# 0021.net
KiCad netlist of a schematic drawn in Altium Designer
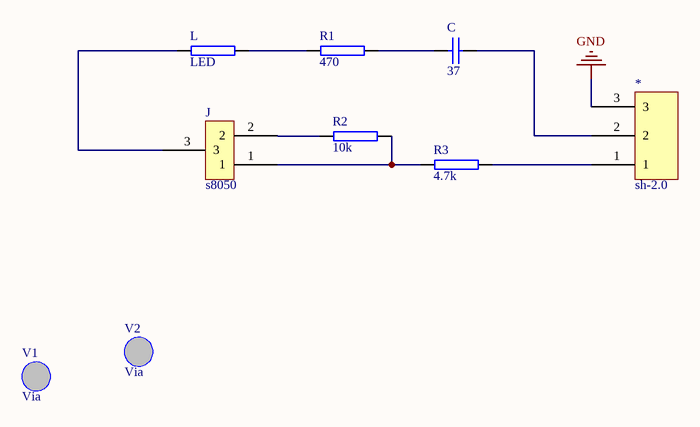
[diagram p0: 0021.SchDoc]

(export (version "E")
  (design (tool "Eeschema 10.0.6"))
  (components
    (comp (ref "*") (value "sh-2.0") (footprint "sh-2.0") (libsource (lib "zhangchong") (part "sh-2.0")))
    (comp (ref "C") (value "37") (footprint "0402") (libsource (lib "gupeng_sch") (part "CAP0402")))
    (comp (ref "J") (value "s8050") (footprint "SOT-23") (libsource (lib "zhangchong") (part "s8050")))
    (comp (ref "L") (value "LED") (footprint "1206") (libsource (lib "PEI_SCH") (part "RES1206")))
    (comp (ref "R1") (value "470") (footprint "0402") (libsource (lib "gupeng_sch") (part "RES0402")))
    (comp (ref "R2") (value "10k") (footprint "0402") (libsource (lib "gupeng_sch") (part "RES0402")))
    (comp (ref "R3") (value "4.7k") (footprint "0402") (libsource (lib "gupeng_sch") (part "RES0402")))
    (comp (ref "V1") (value "Via") (footprint "zhaoyujiu:Via") (libsource (lib "zhaoyujiu") (part "Via")))
    (comp (ref "V2") (value "Via") (footprint "zhaoyujiu:Via") (libsource (lib "zhaoyujiu") (part "Via")))
  )
  (nets
    (net (code "1") (name "GND") (class "Default")
      (node (ref "*") (pin "3") (pinfunction "3_3") (pintype "passive"))
    )
    (net (code "2") (name "Net-(*-Pad1)") (class "Default")
      (node (ref "*") (pin "1") (pinfunction "1_1") (pintype "passive"))
      (node (ref "R3") (pin "2") (pinfunction "2_2") (pintype "passive"))
    )
    (net (code "3") (name "Net-(*-Pad2)") (class "Default")
      (node (ref "*") (pin "2") (pinfunction "2_2") (pintype "passive"))
      (node (ref "C") (pin "2") (pinfunction "2_2") (pintype "passive"))
    )
    (net (code "4") (name "Net-(C-Pad1)") (class "Default")
      (node (ref "C") (pin "1") (pinfunction "1_1") (pintype "passive"))
      (node (ref "R1") (pin "2") (pinfunction "2_2") (pintype "passive"))
    )
    (net (code "5") (name "Net-(J-Pad1)") (class "Default")
      (node (ref "J") (pin "1") (pinfunction "1_1") (pintype "passive"))
      (node (ref "R2") (pin "1") (pinfunction "1_1") (pintype "passive"))
      (node (ref "R3") (pin "1") (pinfunction "1_1") (pintype "passive"))
    )
    (net (code "6") (name "Net-(J-Pad2)") (class "Default")
      (node (ref "J") (pin "2") (pinfunction "2_2") (pintype "passive"))
      (node (ref "R2") (pin "2") (pinfunction "2_2") (pintype "passive"))
    )
    (net (code "7") (name "Net-(J-Pad3)") (class "Default")
      (node (ref "J") (pin "3") (pinfunction "3_3") (pintype "passive"))
      (node (ref "L") (pin "1") (pinfunction "1_1") (pintype "passive"))
    )
    (net (code "8") (name "Net-(L-Pad2)") (class "Default")
      (node (ref "L") (pin "2") (pinfunction "2_2") (pintype "passive"))
      (node (ref "R1") (pin "1") (pinfunction "1_1") (pintype "passive"))
    )
  )
)
